# Airbeamv0_01.net
KiCad netlist of a schematic drawn in EAGLE
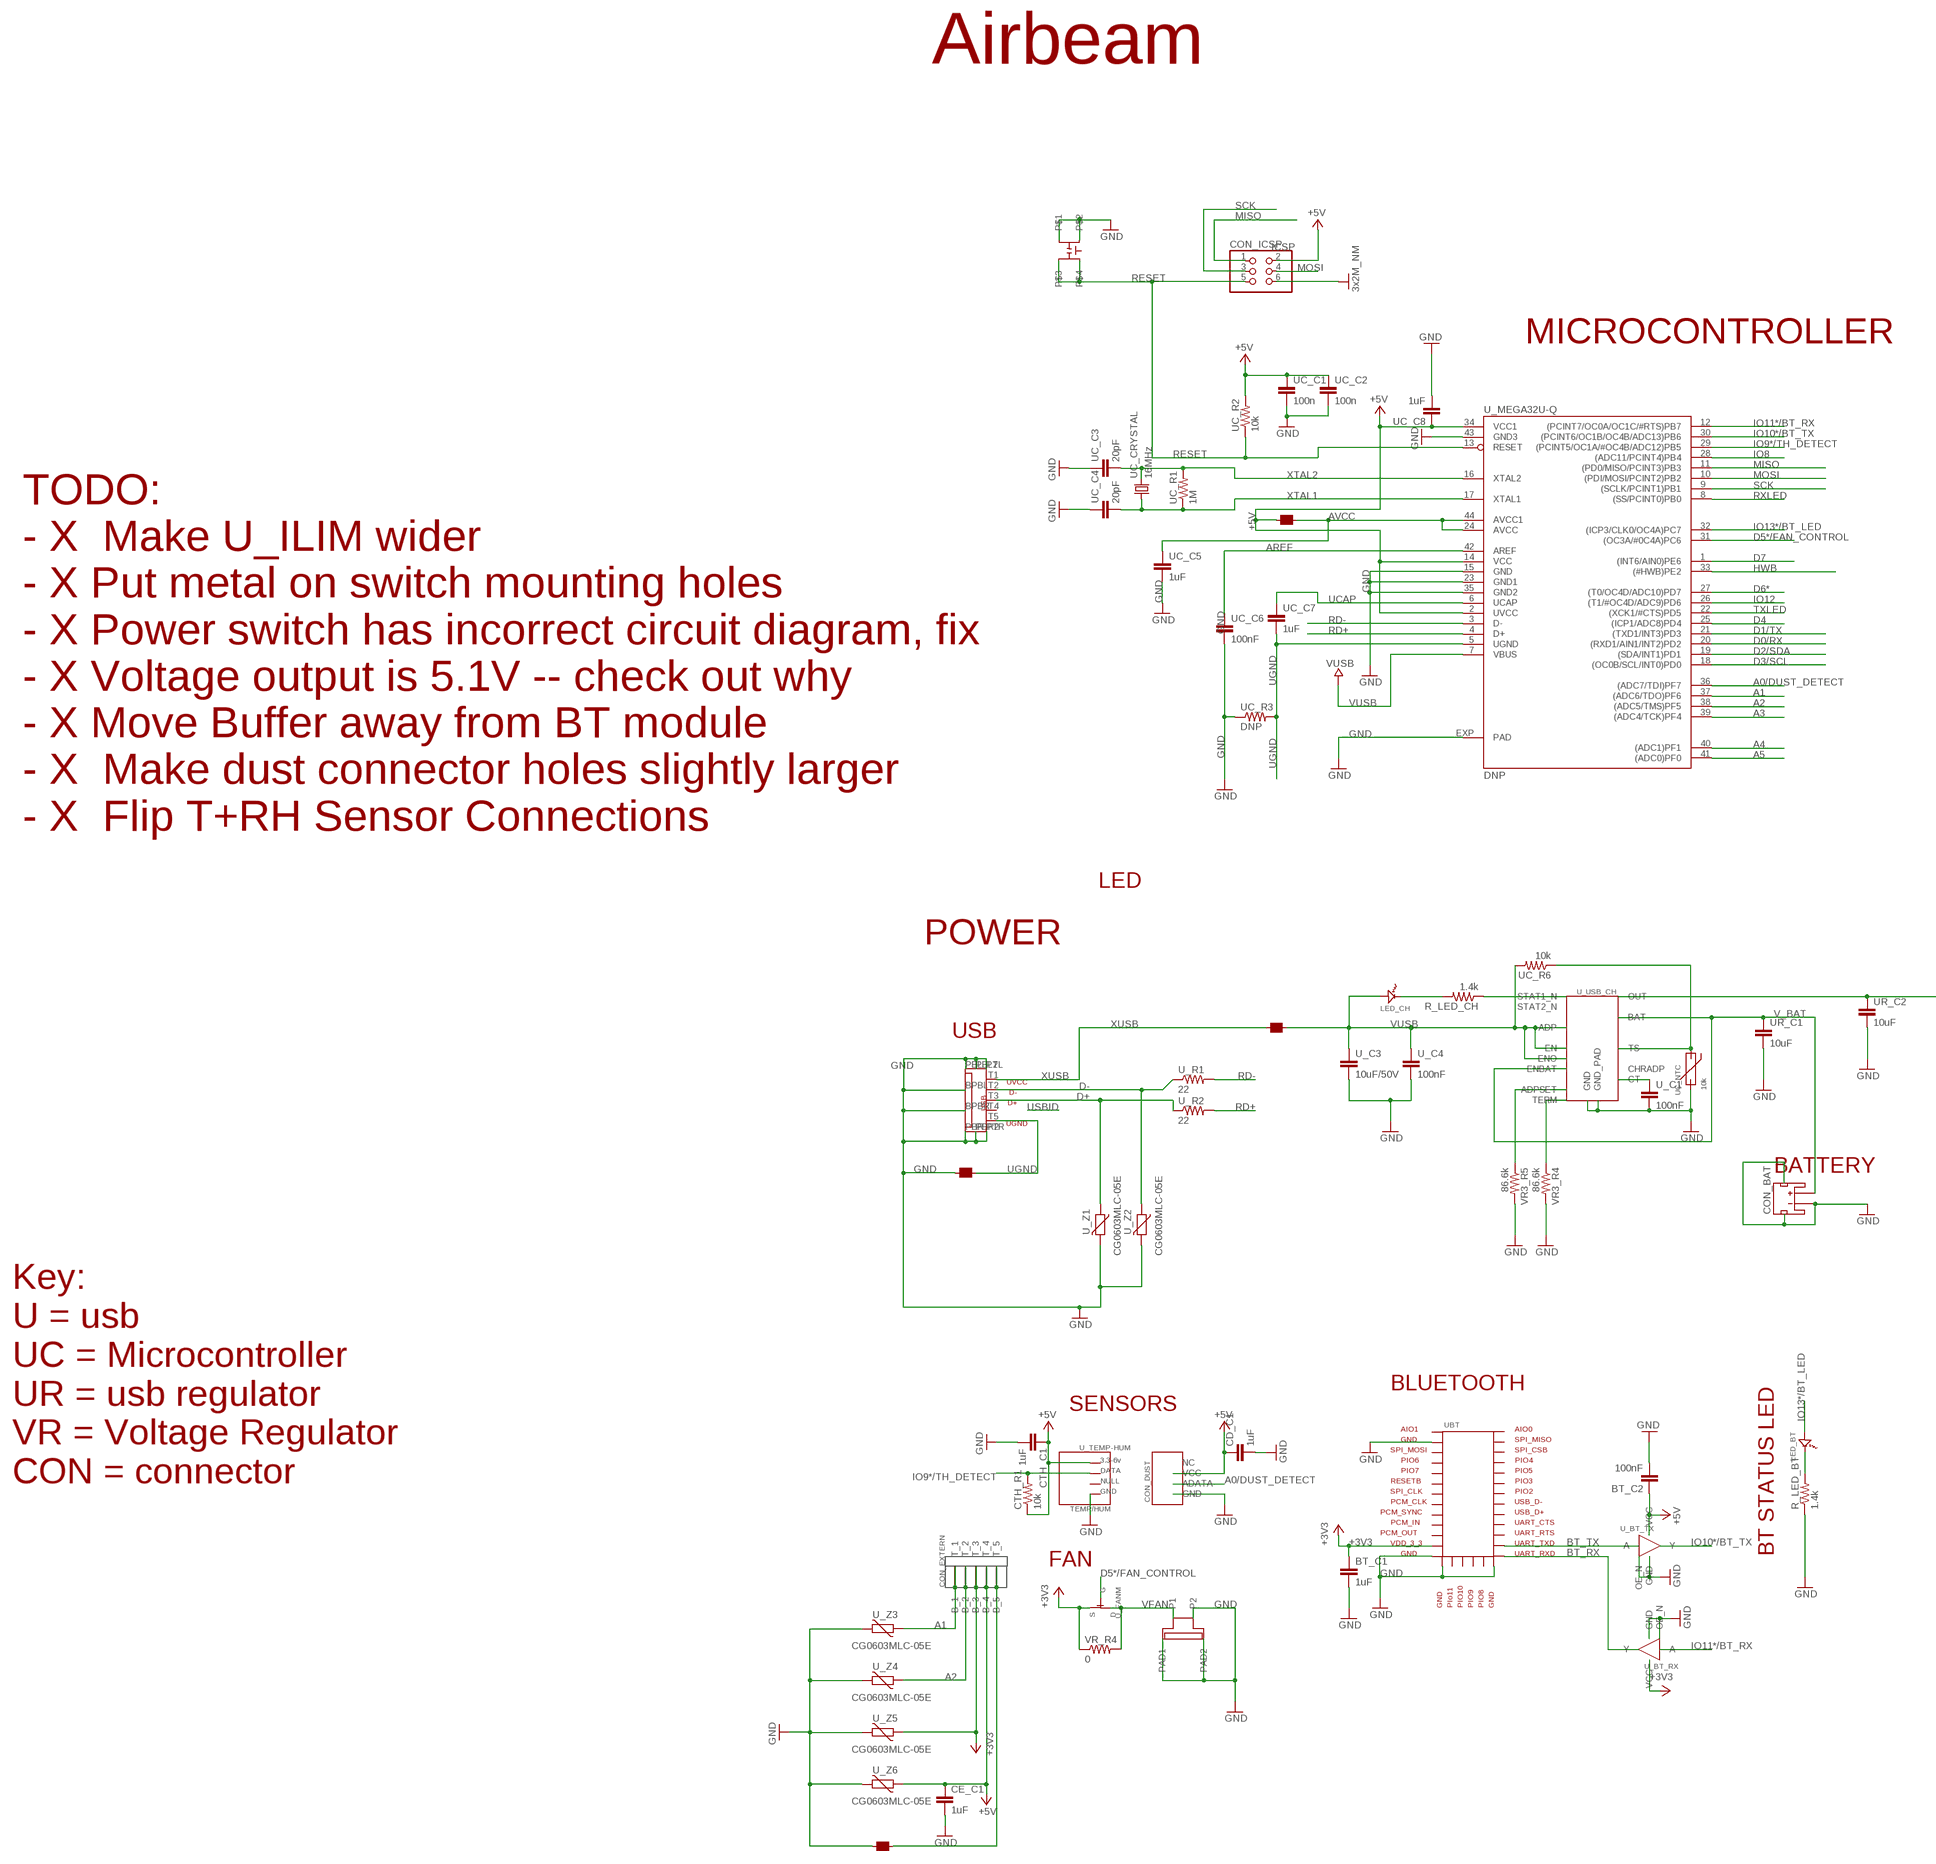
[diagram p0: schematic, sheet 1, part 1 of 2]
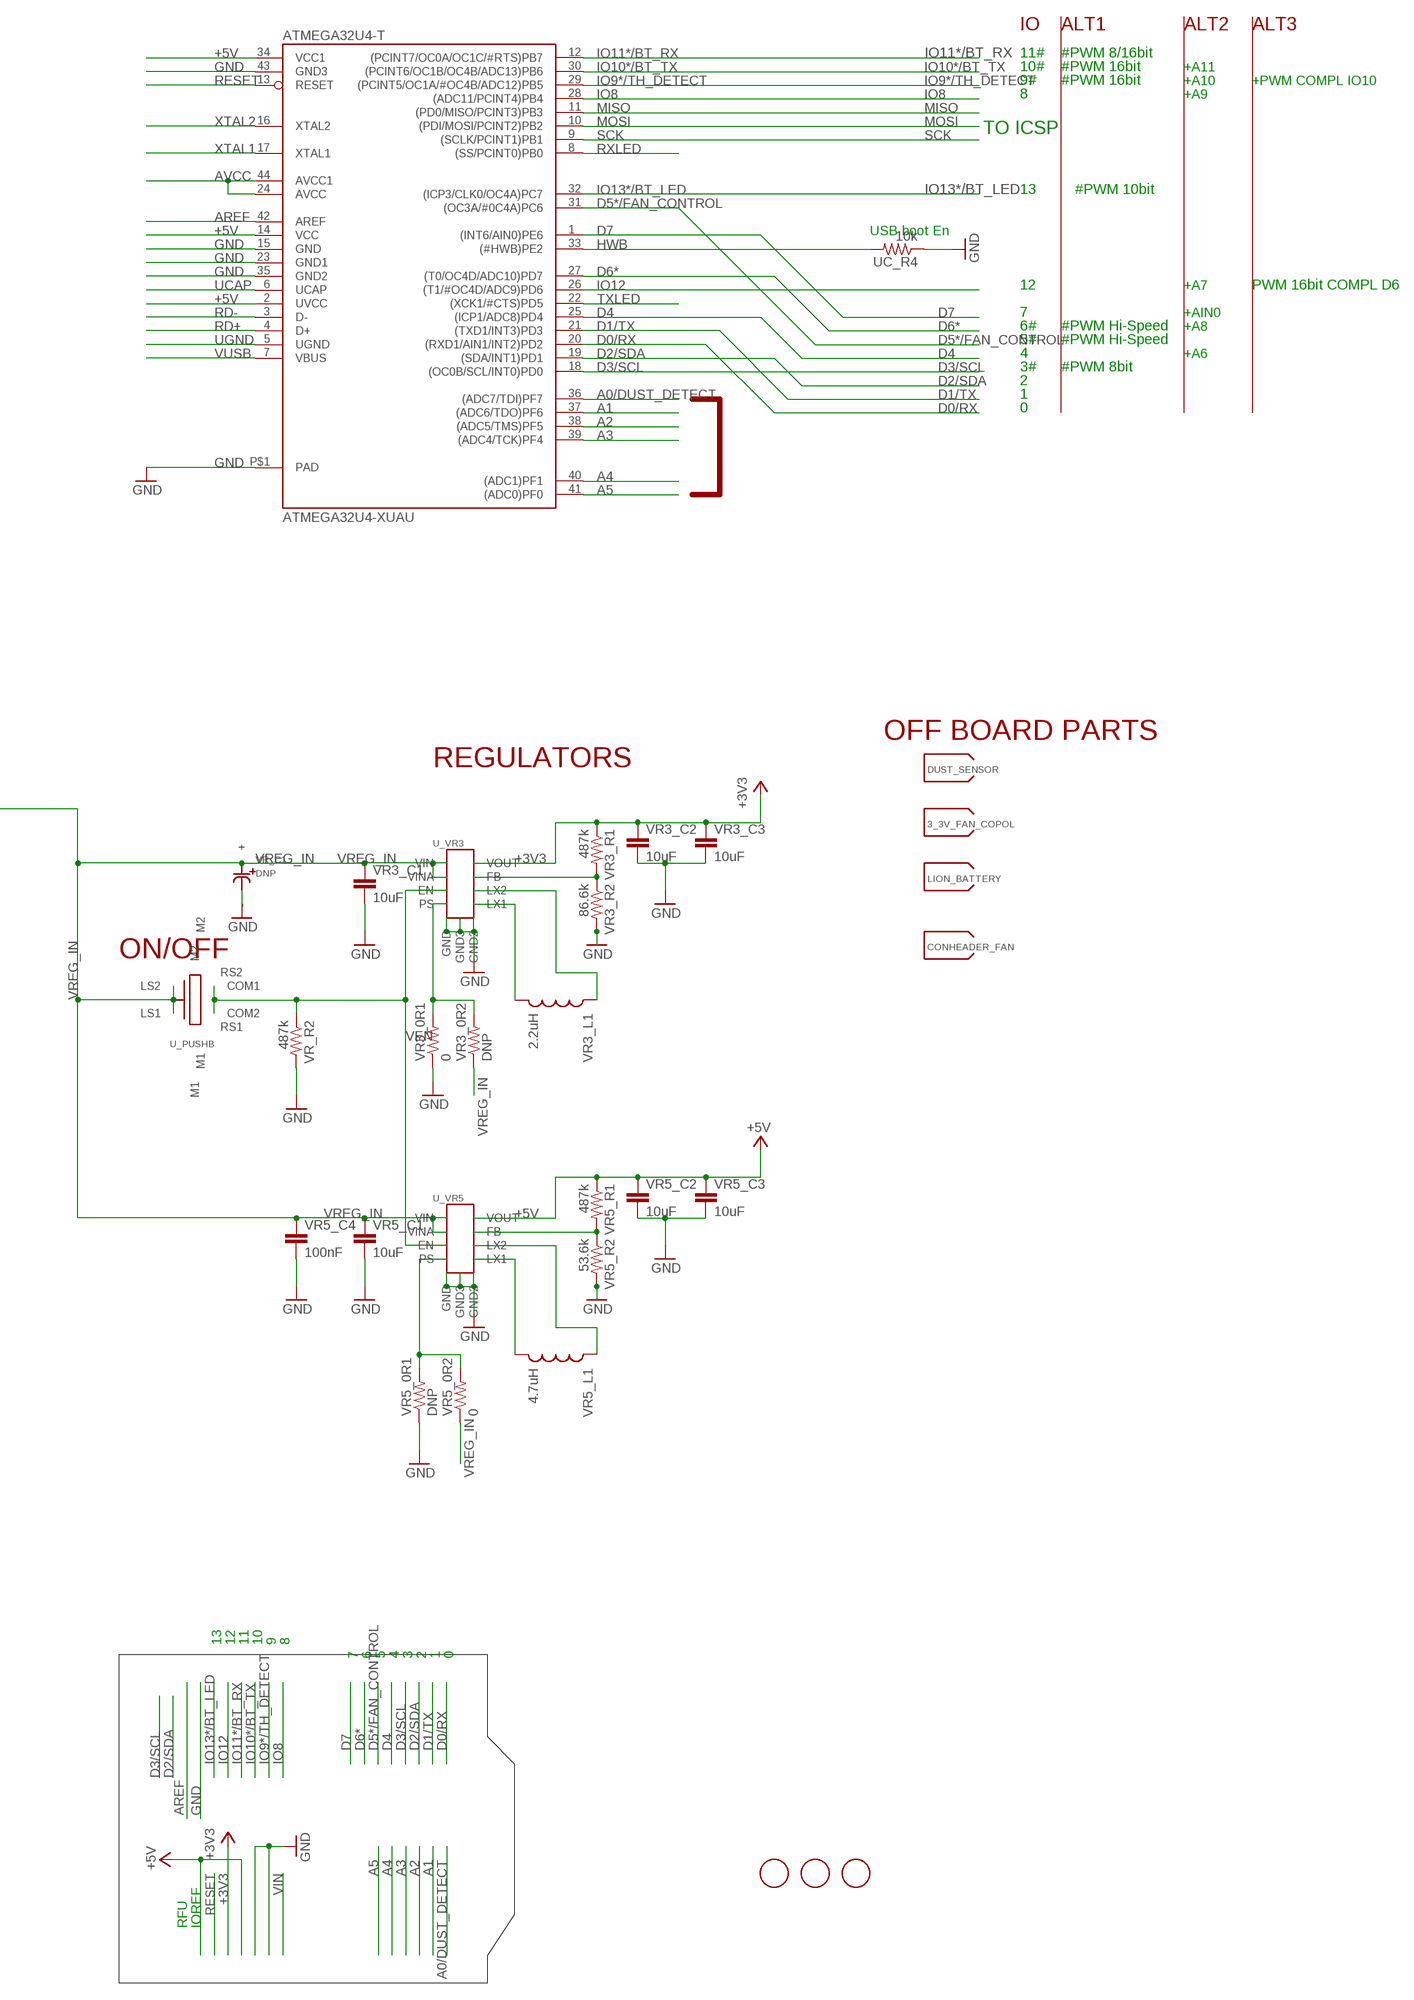
[diagram p1: schematic, sheet 1, part 2 of 2]

(export (version "E")
  (design (tool "Eeschema 10.0.6"))
  (components
    (comp (ref "3_3V_FAN_COPOL")
      (value "OFF_BOARD")
      (footprint "eagle-import:EMPTY")
      (fields (field (name "PARTNO") "F16FB-05LLC/E"))
      (libsource (lib "eagle-import") (part "PART_OFFBOARD"))
    )
    (comp (ref "ATMEGA32U4-T")
      (value "ATMEGA32U4-XUAU")
      (footprint "eagle-import:TQFP44-PAD")
      (fields (field (name "PARTNO") "ATMEGA32U4-AU"))
      (libsource (lib "eagle-import") (part "ATMEGA32U4-XUAU"))
    )
    (comp (ref "BT_C1")
      (value "1uF")
      (footprint "eagle-import:0603-CAP")
      (fields (field (name "PARTNO") "C1608X5R1C105K080AA"))
      (libsource (lib "eagle-import") (part "CAP0603-CAP"))
    )
    (comp (ref "BT_C2")
      (value "100nF")
      (footprint "eagle-import:0603-CAP")
      (fields (field (name "PARTNO") "C1608X7R1E104K080AA"))
      (libsource (lib "eagle-import") (part "CAP0603-CAP"))
    )
    (comp (ref "CA_FB1")
      (value "FERITE_BEAD")
      (footprint "eagle-import:U_FB1")
      (fields (field (name "PARTNO") "MH2029-600Y"))
      (libsource (lib "eagle-import") (part "FERITE_BEAD"))
    )
    (comp (ref "CD_C1")
      (value "1uF")
      (footprint "eagle-import:0603-CAP")
      (fields (field (name "PARTNO") "C1608X5R1C105K080AA"))
      (libsource (lib "eagle-import") (part "CAP0603-CAP"))
    )
    (comp (ref "CE_C1")
      (value "1uF")
      (footprint "eagle-import:0603-CAP")
      (fields (field (name "PARTNO") "C1608X5R1C105K080AA"))
      (libsource (lib "eagle-import") (part "CAP0603-CAP"))
    )
    (comp (ref "CONHEADER_FAN")
      (value "OFF_BOARD")
      (footprint "eagle-import:EMPTY")
      (fields (field (name "PARTNO") "02SUR-32S"))
      (libsource (lib "eagle-import") (part "PART_OFFBOARD"))
    )
    (comp (ref "CON_BAT")
      (value "CON_BAT")
      (footprint "eagle-import:JST-2-SMD")
      (fields (field (name "PARTNO") "S2B-PH-SM4-TB(LF)(SN)"))
      (libsource (lib "eagle-import") (part "JST_2MM_MALE"))
    )
    (comp (ref "CON_DUST")
      (value "CON_DUST")
      (footprint "eagle-import:S4B-EH")
      (fields (field (name "PARTNO") "S4B-EH"))
      (libsource (lib "eagle-import") (part "CON_DUST"))
    )
    (comp (ref "CON_EXTERN")
      (value "TBLOCK_5")
      (footprint "eagle-import:TBLOCK_5")
      (fields (field (name "PARTNO") "1770911"))
      (libsource (lib "eagle-import") (part "TBLOCK_5"))
    )
    (comp (ref "CON_FAN")
      (value "SUR_2PIN")
      (footprint "eagle-import:JST-0.8MM")
      (fields (field (name "PARTNO") "SM02B-SURS-TF"))
      (libsource (lib "eagle-import") (part "SUR_2PIN"))
    )
    (comp (ref "CON_ICSP")
      (value "ICSP")
      (footprint "eagle-import:2X03")
      (fields (field (name "PARTNO") "67997-206HLF "))
      (libsource (lib "eagle-import") (part "PINHD-2X3"))
    )
    (comp (ref "CON_USB")
      (value "USB-FCI")
      (footprint "eagle-import:USB-FCI")
      (fields (field (name "PARTNO") "10103594-0001LF"))
      (libsource (lib "eagle-import") (part "USB-FCI"))
    )
    (comp (ref "CTH_C1")
      (value "1uF")
      (footprint "eagle-import:0603-CAP")
      (fields (field (name "PARTNO") "C1608X5R1C105K080AA"))
      (libsource (lib "eagle-import") (part "CAP0603-CAP"))
    )
    (comp (ref "CTH_R1")
      (value "10k")
      (footprint "eagle-import:0603-RES")
      (fields (field (name "PARTNO") "RC0603JR-0710KL"))
      (libsource (lib "eagle-import") (part "RESISTOR0603-RES"))
    )
    (comp (ref "DUST_SENSOR")
      (value "OFF_BOARD")
      (footprint "eagle-import:EMPTY")
      (fields (field (name "PARTNO") "PPD60PV-T2"))
      (libsource (lib "eagle-import") (part "PART_OFFBOARD"))
    )
    (comp (ref "FID1")
      (value "FIDUCIALMOUNT")
      (footprint "eagle-import:FIDUCIA-MOUNT")
      (fields (field (name "PARTNO") "DNP"))
      (libsource (lib "eagle-import") (part "FIDUCIALMOUNT"))
    )
    (comp (ref "FID2")
      (value "FIDUCIALMOUNT")
      (footprint "eagle-import:FIDUCIA-MOUNT")
      (fields (field (name "PARTNO") "DNP"))
      (libsource (lib "eagle-import") (part "FIDUCIALMOUNT"))
    )
    (comp (ref "FID3")
      (value "FIDUCIALMOUNT")
      (footprint "eagle-import:FIDUCIA-MOUNT")
      (fields (field (name "PARTNO") "DNP"))
      (libsource (lib "eagle-import") (part "FIDUCIALMOUNT"))
    )
    (comp (ref "LED_BT")
      (value "LED")
      (footprint "eagle-import:LED_550")
      (fields (field (name "PARTNO") "550-1107F "))
      (libsource (lib "eagle-import") (part "LED"))
    )
    (comp (ref "LED_CH")
      (value "LED")
      (footprint "eagle-import:LED_550")
      (fields (field (name "PARTNO") "550-1307F"))
      (libsource (lib "eagle-import") (part "LED"))
    )
    (comp (ref "LION_BATTERY")
      (value "OFF_BOARD")
      (footprint "eagle-import:EMPTY")
      (fields (field (name "PARTNO") "585460_2000mAh"))
      (libsource (lib "eagle-import") (part "PART_OFFBOARD"))
    )
    (comp (ref "RESET_SWITCH")
      (value "DNP")
      (footprint "eagle-import:SWITCH_TACTILE")
      (fields (field (name "PARTNO") "TL3315NF250Q"))
      (libsource (lib "eagle-import") (part "SWITCH"))
    )
    (comp (ref "R_LED_BT")
      (value "1.4k")
      (footprint "eagle-import:0603-RES")
      (fields (field (name "PARTNO") "RC0603FR-071K4L"))
      (libsource (lib "eagle-import") (part "RESISTOR0603-RES"))
    )
    (comp (ref "R_LED_CH")
      (value "1.4k")
      (footprint "eagle-import:0603-RES")
      (fields (field (name "PARTNO") "RC0603FR-071K4L"))
      (libsource (lib "eagle-import") (part "RESISTOR0603-RES"))
    )
    (comp (ref "UBT")
      (value "BT-NVC-MDCS42A")
      (footprint "eagle-import:BT_NVC-MDCS42A")
      (fields (field (name "PARTNO") "NVC-MDCS42A"))
      (libsource (lib "eagle-import") (part "BT-NVC-MDCS42A"))
    )
    (comp (ref "UC_C1")
      (value "100n")
      (footprint "eagle-import:0603-CAP")
      (fields (field (name "PARTNO") "C1608X7R1E104K080AA"))
      (libsource (lib "eagle-import") (part "CAP0603-CAP"))
    )
    (comp (ref "UC_C2")
      (value "100n")
      (footprint "eagle-import:0603-CAP")
      (fields (field (name "PARTNO") "C1608X7R1E104K080AA"))
      (libsource (lib "eagle-import") (part "CAP0603-CAP"))
    )
    (comp (ref "UC_C3")
      (value "20pF")
      (footprint "eagle-import:0603-CAP")
      (fields (field (name "PARTNO") "CL10C200JB8NNNC"))
      (libsource (lib "eagle-import") (part "CAP0603-CAP"))
    )
    (comp (ref "UC_C4")
      (value "20pF")
      (footprint "eagle-import:0603-CAP")
      (fields (field (name "PARTNO") "CL10C200JB8NNNC"))
      (libsource (lib "eagle-import") (part "CAP0603-CAP"))
    )
    (comp (ref "UC_C5")
      (value "1uF")
      (footprint "eagle-import:0603-CAP")
      (fields (field (name "PARTNO") "C1608X5R1C105K080AA"))
      (libsource (lib "eagle-import") (part "CAP0603-CAP"))
    )
    (comp (ref "UC_C6")
      (value "100nF")
      (footprint "eagle-import:0603-CAP")
      (fields (field (name "PARTNO") "C1608X7R1E104K080AA"))
      (libsource (lib "eagle-import") (part "CAP0603-CAP"))
    )
    (comp (ref "UC_C7")
      (value "1uF")
      (footprint "eagle-import:0603-CAP")
      (fields (field (name "PARTNO") "C1608X5R1C105K080AA"))
      (libsource (lib "eagle-import") (part "CAP0603-CAP"))
    )
    (comp (ref "UC_C8")
      (value "1uF")
      (footprint "eagle-import:0603-CAP")
      (fields (field (name "PARTNO") "C1608X5R1C105K080AA"))
      (libsource (lib "eagle-import") (part "CAP0603-CAP"))
    )
    (comp (ref "UC_CRYSTAL")
      (value "16MHz")
      (footprint "eagle-import:HC49UP")
      (fields (field (name "PARTNO") "ECS-160-20-3X-TR "))
      (libsource (lib "eagle-import") (part "CRYSTALSMD"))
    )
    (comp (ref "UC_NTC")
      (value "10k")
      (footprint "eagle-import:0402")
      (fields (field (name "PARTNO") "ERT-J0EM103J ") (field (name "PARTNO_1") "ERT-J0EM103J"))
      (libsource (lib "eagle-import") (part "THERMISTOR0402"))
    )
    (comp (ref "UC_R1")
      (value "1M")
      (footprint "eagle-import:0603-RES")
      (fields (field (name "PARTNO") "RC0603FR-071ML"))
      (libsource (lib "eagle-import") (part "RESISTOR0603-RES"))
    )
    (comp (ref "UC_R2")
      (value "10k")
      (footprint "eagle-import:0603-RES")
      (fields (field (name "PARTNO") "RC0603JR-0710KL"))
      (libsource (lib "eagle-import") (part "RESISTOR0603-RES"))
    )
    (comp (ref "UC_R3")
      (value "DNP")
      (footprint "eagle-import:0603-RES")
      (fields (field (name "PARTNO") "RC0603JR-070RL"))
      (libsource (lib "eagle-import") (part "RESISTOR0603-RES"))
    )
    (comp (ref "UC_R4")
      (value "10k")
      (footprint "eagle-import:0603-RES")
      (fields (field (name "PARTNO") "RC0603JR-0710KL"))
      (libsource (lib "eagle-import") (part "RESISTOR0603-RES"))
    )
    (comp (ref "UC_R6")
      (value "10k")
      (footprint "eagle-import:0603-RES")
      (fields (field (name "PARTNO") "RC0603JR-0710KL"))
      (libsource (lib "eagle-import") (part "RESISTOR0603-RES"))
    )
    (comp (ref "UR_C1")
      (value "10uF")
      (footprint "eagle-import:0805")
      (fields (field (name "PARTNO") "C2012X5R1C106K085AC"))
      (libsource (lib "eagle-import") (part "CAP0805"))
    )
    (comp (ref "UR_C2")
      (value "10uF")
      (footprint "eagle-import:0805")
      (fields (field (name "PARTNO") "C2012X5R1C106K085AC"))
      (libsource (lib "eagle-import") (part "CAP0805"))
    )
    (comp (ref "U_BT_RX")
      (value "V_BUFFER")
      (footprint "eagle-import:SOT23-5")
      (fields (field (name "PARTNO") "SN74LVC1G125DBVR"))
      (libsource (lib "eagle-import") (part "V_BUFFER"))
    )
    (comp (ref "U_BT_TX")
      (value "V_BUFFER")
      (footprint "eagle-import:SOT23-5")
      (fields (field (name "PARTNO") "SN74LVC1G125DBVR"))
      (libsource (lib "eagle-import") (part "V_BUFFER"))
    )
    (comp (ref "U_C1")
      (value "100nF")
      (footprint "eagle-import:0603-CAP")
      (fields (field (name "PARTNO") "C1608X7R1E104K080AA"))
      (libsource (lib "eagle-import") (part "CAP0603-CAP"))
    )
    (comp (ref "U_C3")
      (value "10uF/50V")
      (footprint "eagle-import:1206")
      (fields (field (name "PARTNO") "CL31A106KBHNNNE "))
      (libsource (lib "eagle-import") (part "CAP1206"))
    )
    (comp (ref "U_C4")
      (value "100nF")
      (footprint "eagle-import:0603-CAP")
      (fields (field (name "PARTNO") "CC0603ZRY5V9BB104"))
      (libsource (lib "eagle-import") (part "CAP0603-CAP"))
    )
    (comp (ref "U_FANM")
      (value "DNP")
      (footprint "eagle-import:SOT23")
      (fields (field (name "PARTNO") "NDS331N"))
      (libsource (lib "eagle-import") (part "MOSFET-N"))
    )
    (comp (ref "U_FB1")
      (value "FERITE_BEAD")
      (footprint "eagle-import:U_FB1")
      (fields (field (name "PARTNO") "MH2029-600Y"))
      (libsource (lib "eagle-import") (part "FERITE_BEAD"))
    )
    (comp (ref "U_FB2")
      (value "FERITE_BEAD")
      (footprint "eagle-import:U_FB1")
      (fields (field (name "PARTNO") "MH2029-600Y"))
      (libsource (lib "eagle-import") (part "FERITE_BEAD"))
    )
    (comp (ref "U_FB3")
      (value "FERITE_BEAD")
      (footprint "eagle-import:U_FB1")
      (fields (field (name "PARTNO") "MH2029-600Y"))
      (libsource (lib "eagle-import") (part "FERITE_BEAD"))
    )
    (comp (ref "U_MEGA32U-Q")
      (value "DNP")
      (footprint "eagle-import:QFN44ML7X7")
      (fields (field (name "PARTNO") "ATMEGA32U4-MU "))
      (libsource (lib "eagle-import") (part "ATMEGA32U4-XUMU"))
    )
    (comp (ref "U_PUSHB")
      (value "PUSHBUTTON")
      (footprint "eagle-import:PUSHBUTTON")
      (fields (field (name "PARTNO") "LC2259EENP"))
      (libsource (lib "eagle-import") (part "PUSHBUTTON"))
    )
    (comp (ref "U_R1")
      (value "22")
      (footprint "eagle-import:0603-RES")
      (fields (field (name "PARTNO") "RC0603JR-0722RL"))
      (libsource (lib "eagle-import") (part "RESISTOR0603-RES"))
    )
    (comp (ref "U_R2")
      (value "22")
      (footprint "eagle-import:0603-RES")
      (fields (field (name "PARTNO") "RC0603JR-0722RL"))
      (libsource (lib "eagle-import") (part "RESISTOR0603-RES"))
    )
    (comp (ref "U_TEMP-HUM")
      (value "RHT03")
      (footprint "eagle-import:RHT03")
      (fields (field (name "PARTNO") "RHT03 "))
      (libsource (lib "eagle-import") (part "RHT03"))
    )
    (comp (ref "U_USB_CH")
      (value "USB-BATTERY_LOAD")
      (footprint "eagle-import:TDFN33-14")
      (fields (field (name "PARTNO") "AAT3672IWO-4.2-1-T1") (field (name "PARTNO_1") "AAT3672IWO-4.2-1-T1"))
      (libsource (lib "eagle-import") (part "USB-BATTERY_LOAD"))
    )
    (comp (ref "U_VR3")
      (value "VREG-RTEC6150")
      (footprint "eagle-import:WFDFN-10")
      (fields (field (name "PARTNO") "RT6150BGQW"))
      (libsource (lib "eagle-import") (part "VREG-RTEC6150"))
    )
    (comp (ref "U_VR5")
      (value "VREG-RTEC6150")
      (footprint "eagle-import:WFDFN-10")
      (fields (field (name "PARTNO") "RT6150BGQW"))
      (libsource (lib "eagle-import") (part "VREG-RTEC6150"))
    )
    (comp (ref "U_Z1")
      (value "CG0603MLC-05E")
      (footprint "eagle-import:CT_CN0603")
      (libsource (lib "eagle-import") (part "VARISTORCN0603"))
    )
    (comp (ref "U_Z2")
      (value "CG0603MLC-05E")
      (footprint "eagle-import:CT_CN0603")
      (libsource (lib "eagle-import") (part "VARISTORCN0603"))
    )
    (comp (ref "U_Z3")
      (value "CG0603MLC-05E")
      (footprint "eagle-import:CT_CN0603")
      (libsource (lib "eagle-import") (part "VARISTORCN0603"))
    )
    (comp (ref "U_Z4")
      (value "CG0603MLC-05E")
      (footprint "eagle-import:CT_CN0603")
      (libsource (lib "eagle-import") (part "VARISTORCN0603"))
    )
    (comp (ref "U_Z5")
      (value "CG0603MLC-05E")
      (footprint "eagle-import:CT_CN0603")
      (libsource (lib "eagle-import") (part "VARISTORCN0603"))
    )
    (comp (ref "U_Z6")
      (value "CG0603MLC-05E")
      (footprint "eagle-import:CT_CN0603")
      (libsource (lib "eagle-import") (part "VARISTORCN0603"))
    )
    (comp (ref "VR3_0R1")
      (value "0")
      (footprint "eagle-import:0603-RES")
      (fields (field (name "PARTNO") "RC0603JR-070RL"))
      (libsource (lib "eagle-import") (part "RESISTOR0603-RES"))
    )
    (comp (ref "VR3_0R2")
      (value "DNP")
      (footprint "eagle-import:0603-RES")
      (fields (field (name "PARTNO") "RC0603JR-070RL"))
      (libsource (lib "eagle-import") (part "RESISTOR0603-RES"))
    )
    (comp (ref "VR3_C1")
      (value "10uF")
      (footprint "eagle-import:0805")
      (fields (field (name "PARTNO") "C2012X5R1C106K085AC"))
      (libsource (lib "eagle-import") (part "CAP0805"))
    )
    (comp (ref "VR3_C2")
      (value "10uF")
      (footprint "eagle-import:0805")
      (fields (field (name "PARTNO") "C2012X5R1C106K085AC"))
      (libsource (lib "eagle-import") (part "CAP0805"))
    )
    (comp (ref "VR3_C3")
      (value "10uF")
      (footprint "eagle-import:0805")
      (fields (field (name "PARTNO") "C2012X5R1C106K085AC"))
      (libsource (lib "eagle-import") (part "CAP0805"))
    )
    (comp (ref "VR3_L1")
      (value "2.2uH")
      (footprint "eagle-import:1210")
      (fields (field (name "PARTNO") "BRL3225T2R2M"))
      (libsource (lib "eagle-import") (part "INDUCTOR1210"))
    )
    (comp (ref "VR3_R1")
      (value "487k")
      (footprint "eagle-import:0603-RES")
      (fields (field (name "PARTNO") "ERJ-3EKF4873V"))
      (libsource (lib "eagle-import") (part "RESISTOR0603"))
    )
    (comp (ref "VR3_R2")
      (value "86.6k")
      (footprint "eagle-import:0603-RES")
      (fields (field (name "PARTNO") "ERJ-3EKF8662V"))
      (libsource (lib "eagle-import") (part "RESISTOR0603"))
    )
    (comp (ref "VR3_R4")
      (value "86.6k")
      (footprint "eagle-import:0603-RES")
      (fields (field (name "PARTNO") "ERJ-3EKF8662V"))
      (libsource (lib "eagle-import") (part "RESISTOR0603"))
    )
    (comp (ref "VR3_R5")
      (value "86.6k")
      (footprint "eagle-import:0603-RES")
      (fields (field (name "PARTNO") "ERJ-3EKF8662V"))
      (libsource (lib "eagle-import") (part "RESISTOR0603"))
    )
    (comp (ref "VR5_0R1")
      (value "DNP")
      (footprint "eagle-import:0603-RES")
      (fields (field (name "PARTNO") "RC0603JR-070RL"))
      (libsource (lib "eagle-import") (part "RESISTOR0603-RES"))
    )
    (comp (ref "VR5_0R2")
      (value "0")
      (footprint "eagle-import:0603-RES")
      (fields (field (name "PARTNO") "RC0603JR-070RL"))
      (libsource (lib "eagle-import") (part "RESISTOR0603-RES"))
    )
    (comp (ref "VR5_C1")
      (value "10uF")
      (footprint "eagle-import:0805")
      (fields (field (name "PARTNO") "C2012X5R1C106K085AC"))
      (libsource (lib "eagle-import") (part "CAP0805"))
    )
    (comp (ref "VR5_C2")
      (value "10uF")
      (footprint "eagle-import:0805")
      (fields (field (name "PARTNO") "C2012X5R1C106K085AC"))
      (libsource (lib "eagle-import") (part "CAP0805"))
    )
    (comp (ref "VR5_C3")
      (value "10uF")
      (footprint "eagle-import:0805")
      (fields (field (name "PARTNO") "C2012X5R1C106K085AC"))
      (libsource (lib "eagle-import") (part "CAP0805"))
    )
    (comp (ref "VR5_C4")
      (value "100nF")
      (footprint "eagle-import:0603-CAP")
      (fields (field (name "PARTNO") "C1608X7R1E104K080AA"))
      (libsource (lib "eagle-import") (part "CAP0603-CAP"))
    )
    (comp (ref "VR5_L1")
      (value "4.7uH")
      (footprint "eagle-import:1210")
      (fields (field (name "PARTNO") "CBC3225T4R7MR"))
      (libsource (lib "eagle-import") (part "INDUCTOR1210"))
    )
    (comp (ref "VR5_R1")
      (value "487k")
      (footprint "eagle-import:0603-RES")
      (fields (field (name "PARTNO") "ERJ-3EKF4873V"))
      (libsource (lib "eagle-import") (part "RESISTOR0603"))
    )
    (comp (ref "VR5_R2")
      (value "53.6k")
      (footprint "eagle-import:0603-RES")
      (fields (field (name "PARTNO") "RC0805FR-0753K6L"))
      (libsource (lib "eagle-import") (part "RESISTOR0603"))
    )
    (comp (ref "VR_C1")
      (value "DNP")
      (footprint "eagle-import:2917_CAP")
      (fields (field (name "PARTNO") "T491D107K010AT "))
      (libsource (lib "eagle-import") (part "CAP_POL120UF"))
    )
    (comp (ref "VR_R2")
      (value "487k")
      (footprint "eagle-import:0603-RES")
      (fields (field (name "PARTNO") "ERJ-3EKF4873V"))
      (libsource (lib "eagle-import") (part "RESISTOR0603"))
    )
    (comp (ref "VR_R4")
      (value "0")
      (footprint "eagle-import:0603-RES")
      (fields (field (name "PARTNO") "RC0603JR-070RL"))
      (libsource (lib "eagle-import") (part "RESISTOR0603"))
    )
  )
  (nets
    (net (code "1") (name "+3V3") (class "Default")
      (node (ref "BT_C1") (pin "1") (pinfunction "1_1") (pintype "passive"))
      (node (ref "CON_EXTERN") (pin "B_3") (pinfunction "B_3_B_3") (pintype "bidirectional"))
      (node (ref "CON_EXTERN") (pin "T_3") (pinfunction "T_3_T_3") (pintype "bidirectional"))
      (node (ref "UBT") (pin "P$12") (pinfunction "P$12_P$12") (pintype "bidirectional"))
      (node (ref "U_BT_RX") (pin "5") (pinfunction "VCC_5") (pintype "bidirectional"))
      (node (ref "U_FANM") (pin "2") (pinfunction "P$2_2") (pintype "bidirectional"))
      (node (ref "U_VR3") (pin "P$1") (pinfunction "VOUT_P$1") (pintype "bidirectional"))
      (node (ref "U_Z5") (pin "1") (pinfunction "1_1") (pintype "passive"))
      (node (ref "VR3_C2") (pin "1") (pinfunction "1_1") (pintype "passive"))
      (node (ref "VR3_C3") (pin "1") (pinfunction "1_1") (pintype "passive"))
      (node (ref "VR3_R1") (pin "1") (pinfunction "1_1") (pintype "passive"))
      (node (ref "VR_R4") (pin "1") (pinfunction "1_1") (pintype "passive"))
    )
    (net (code "2") (name "+5V") (class "Default")
      (node (ref "ATMEGA32U4-T") (pin "14") (pinfunction "VCC_14") (pintype "power_in"))
      (node (ref "ATMEGA32U4-T") (pin "2") (pinfunction "UVCC_2") (pintype "power_in"))
      (node (ref "ATMEGA32U4-T") (pin "34") (pinfunction "VCC1_34") (pintype "power_in"))
      (node (ref "BT_C2") (pin "1") (pinfunction "1_1") (pintype "passive"))
      (node (ref "CD_C1") (pin "1") (pinfunction "1_1") (pintype "passive"))
      (node (ref "CE_C1") (pin "1") (pinfunction "1_1") (pintype "passive"))
      (node (ref "CON_DUST") (pin "P$3") (pinfunction "VCC_P$3") (pintype "bidirectional"))
      (node (ref "CON_EXTERN") (pin "B_4") (pinfunction "B_4_B_4") (pintype "bidirectional"))
      (node (ref "CON_EXTERN") (pin "T_4") (pinfunction "T_4_T_4") (pintype "bidirectional"))
      (node (ref "CON_ICSP") (pin "2") (pinfunction "2_2") (pintype "passive"))
      (node (ref "CTH_C1") (pin "1") (pinfunction "1_1") (pintype "passive"))
      (node (ref "CTH_R1") (pin "1") (pinfunction "1_1") (pintype "passive"))
      (node (ref "UC_C1") (pin "1") (pinfunction "1_1") (pintype "passive"))
      (node (ref "UC_C2") (pin "1") (pinfunction "1_1") (pintype "passive"))
      (node (ref "UC_C8") (pin "1") (pinfunction "1_1") (pintype "passive"))
      (node (ref "UC_R2") (pin "2") (pinfunction "2_2") (pintype "passive"))
      (node (ref "U_BT_TX") (pin "5") (pinfunction "VCC_5") (pintype "bidirectional"))
      (node (ref "U_FB2") (pin "P$1") (pinfunction "P$1_P$1") (pintype "passive"))
      (node (ref "U_MEGA32U-Q") (pin "14") (pinfunction "VCC_14") (pintype "power_in"))
      (node (ref "U_MEGA32U-Q") (pin "2") (pinfunction "UVCC_2") (pintype "power_in"))
      (node (ref "U_MEGA32U-Q") (pin "34") (pinfunction "VCC1_34") (pintype "power_in"))
      (node (ref "U_TEMP-HUM") (pin "P$1") (pinfunction "P$1_P$1") (pintype "bidirectional"))
      (node (ref "U_VR5") (pin "P$1") (pinfunction "VOUT_P$1") (pintype "bidirectional"))
      (node (ref "U_Z6") (pin "1") (pinfunction "1_1") (pintype "passive"))
      (node (ref "VR5_C2") (pin "1") (pinfunction "1_1") (pintype "passive"))
      (node (ref "VR5_C3") (pin "1") (pinfunction "1_1") (pintype "passive"))
      (node (ref "VR5_R1") (pin "1") (pinfunction "1_1") (pintype "passive"))
    )
    (net (code "3") (name "/A0{slash}DUST_DETECT") (class "Default")
      (node (ref "ATMEGA32U4-T") (pin "36") (pinfunction "(ADC7/TDI)PF7_36") (pintype "bidirectional"))
      (node (ref "CON_DUST") (pin "P$2") (pinfunction "ADATA_P$2") (pintype "bidirectional"))
      (node (ref "U_MEGA32U-Q") (pin "36") (pinfunction "(ADC7/TDI)PF7_36") (pintype "bidirectional"))
    )
    (net (code "4") (name "/A1") (class "Default")
      (node (ref "ATMEGA32U4-T") (pin "37") (pinfunction "(ADC6/TDO)PF6_37") (pintype "bidirectional"))
      (node (ref "CON_EXTERN") (pin "B_1") (pinfunction "B_1_B_1") (pintype "bidirectional"))
      (node (ref "CON_EXTERN") (pin "T_1") (pinfunction "T_1_T_1") (pintype "bidirectional"))
      (node (ref "U_MEGA32U-Q") (pin "37") (pinfunction "(ADC6/TDO)PF6_37") (pintype "bidirectional"))
      (node (ref "U_Z3") (pin "1") (pinfunction "1_1") (pintype "passive"))
    )
    (net (code "5") (name "/A2") (class "Default")
      (node (ref "ATMEGA32U4-T") (pin "38") (pinfunction "(ADC5/TMS)PF5_38") (pintype "bidirectional"))
      (node (ref "CON_EXTERN") (pin "B_2") (pinfunction "B_2_B_2") (pintype "bidirectional"))
      (node (ref "CON_EXTERN") (pin "T_2") (pinfunction "T_2_T_2") (pintype "bidirectional"))
      (node (ref "U_MEGA32U-Q") (pin "38") (pinfunction "(ADC5/TMS)PF5_38") (pintype "bidirectional"))
      (node (ref "U_Z4") (pin "1") (pinfunction "1_1") (pintype "passive"))
    )
    (net (code "6") (name "/A3") (class "Default")
      (node (ref "ATMEGA32U4-T") (pin "39") (pinfunction "(ADC4/TCK)PF4_39") (pintype "bidirectional"))
      (node (ref "U_MEGA32U-Q") (pin "39") (pinfunction "(ADC4/TCK)PF4_39") (pintype "bidirectional"))
    )
    (net (code "7") (name "/A4") (class "Default")
      (node (ref "ATMEGA32U4-T") (pin "40") (pinfunction "(ADC1)PF1_40") (pintype "bidirectional"))
      (node (ref "U_MEGA32U-Q") (pin "40") (pinfunction "(ADC1)PF1_40") (pintype "bidirectional"))
    )
    (net (code "8") (name "/A5") (class "Default")
      (node (ref "ATMEGA32U4-T") (pin "41") (pinfunction "(ADC0)PF0_41") (pintype "bidirectional"))
      (node (ref "U_MEGA32U-Q") (pin "41") (pinfunction "(ADC0)PF0_41") (pintype "bidirectional"))
    )
    (net (code "9") (name "/AREF") (class "Default")
      (node (ref "ATMEGA32U4-T") (pin "42") (pinfunction "AREF_42") (pintype "power_in"))
      (node (ref "UC_C6") (pin "1") (pinfunction "1_1") (pintype "passive"))
      (node (ref "U_MEGA32U-Q") (pin "42") (pinfunction "AREF_42") (pintype "power_in"))
    )
    (net (code "10") (name "/AVCC") (class "Default")
      (node (ref "ATMEGA32U4-T") (pin "24") (pinfunction "AVCC_24") (pintype "power_in"))
      (node (ref "ATMEGA32U4-T") (pin "44") (pinfunction "AVCC1_44") (pintype "power_in"))
      (node (ref "UC_C5") (pin "1") (pinfunction "1_1") (pintype "passive"))
      (node (ref "U_FB2") (pin "P$2") (pinfunction "P$2_P$2") (pintype "passive"))
      (node (ref "U_MEGA32U-Q") (pin "24") (pinfunction "AVCC_24") (pintype "power_in"))
      (node (ref "U_MEGA32U-Q") (pin "44") (pinfunction "AVCC1_44") (pintype "power_in"))
    )
    (net (code "11") (name "/BT_RX") (class "Default")
      (node (ref "UBT") (pin "P$20") (pinfunction "P$20_P$20") (pintype "bidirectional"))
      (node (ref "U_BT_RX") (pin "4") (pinfunction "Y_4") (pintype "bidirectional"))
    )
    (net (code "12") (name "/BT_TX") (class "Default")
      (node (ref "UBT") (pin "P$21") (pinfunction "P$21_P$21") (pintype "bidirectional"))
      (node (ref "U_BT_TX") (pin "2") (pinfunction "A_2") (pintype "bidirectional"))
    )
    (net (code "13") (name "/D+") (class "Default")
      (node (ref "CON_USB") (pin "T3") (pinfunction "T3_T3") (pintype "bidirectional"))
      (node (ref "U_R2") (pin "1") (pinfunction "1_1") (pintype "passive"))
      (node (ref "U_Z1") (pin "1") (pinfunction "1_1") (pintype "passive"))
    )
    (net (code "14") (name "/D-") (class "Default")
      (node (ref "CON_USB") (pin "T2") (pinfunction "T2_T2") (pintype "bidirectional"))
      (node (ref "U_R1") (pin "1") (pinfunction "1_1") (pintype "passive"))
      (node (ref "U_Z2") (pin "1") (pinfunction "1_1") (pintype "passive"))
    )
    (net (code "15") (name "/D0{slash}RX") (class "Default")
      (node (ref "ATMEGA32U4-T") (pin "20") (pinfunction "(RXD1/AIN1/INT2)PD2_20") (pintype "bidirectional"))
      (node (ref "U_MEGA32U-Q") (pin "20") (pinfunction "(RXD1/AIN1/INT2)PD2_20") (pintype "bidirectional"))
    )
    (net (code "16") (name "/D1{slash}TX") (class "Default")
      (node (ref "ATMEGA32U4-T") (pin "21") (pinfunction "(TXD1/INT3)PD3_21") (pintype "bidirectional"))
      (node (ref "U_MEGA32U-Q") (pin "21") (pinfunction "(TXD1/INT3)PD3_21") (pintype "bidirectional"))
    )
    (net (code "17") (name "/D2{slash}SDA") (class "Default")
      (node (ref "ATMEGA32U4-T") (pin "19") (pinfunction "(SDA/INT1)PD1_19") (pintype "bidirectional"))
      (node (ref "U_MEGA32U-Q") (pin "19") (pinfunction "(SDA/INT1)PD1_19") (pintype "bidirectional"))
    )
    (net (code "18") (name "/D3{slash}SCL") (class "Default")
      (node (ref "ATMEGA32U4-T") (pin "18") (pinfunction "(OC0B/SCL/INT0)PD0_18") (pintype "bidirectional"))
      (node (ref "U_MEGA32U-Q") (pin "18") (pinfunction "(OC0B/SCL/INT0)PD0_18") (pintype "bidirectional"))
    )
    (net (code "19") (name "/D4") (class "Default")
      (node (ref "ATMEGA32U4-T") (pin "25") (pinfunction "(ICP1/ADC8)PD4_25") (pintype "bidirectional"))
      (node (ref "U_MEGA32U-Q") (pin "25") (pinfunction "(ICP1/ADC8)PD4_25") (pintype "bidirectional"))
    )
    (net (code "20") (name "/D5*{slash}FAN_CONTROL") (class "Default")
      (node (ref "ATMEGA32U4-T") (pin "31") (pinfunction "(OC3A/#0C4A)PC6_31") (pintype "bidirectional"))
      (node (ref "U_FANM") (pin "1") (pinfunction "P$1_1") (pintype "bidirectional"))
      (node (ref "U_MEGA32U-Q") (pin "31") (pinfunction "(OC3A/#0C4A)PC6_31") (pintype "bidirectional"))
    )
    (net (code "21") (name "/D6*") (class "Default")
      (node (ref "ATMEGA32U4-T") (pin "27") (pinfunction "(T0/OC4D/ADC10)PD7_27") (pintype "bidirectional"))
      (node (ref "U_MEGA32U-Q") (pin "27") (pinfunction "(T0/OC4D/ADC10)PD7_27") (pintype "bidirectional"))
    )
    (net (code "22") (name "/D7") (class "Default")
      (node (ref "ATMEGA32U4-T") (pin "1") (pinfunction "(INT6/AIN0)PE6_1") (pintype "bidirectional"))
      (node (ref "U_MEGA32U-Q") (pin "1") (pinfunction "(INT6/AIN0)PE6_1") (pintype "bidirectional"))
    )
    (net (code "23") (name "/HWB") (class "Default")
      (node (ref "ATMEGA32U4-T") (pin "33") (pinfunction "(#HWB)PE2_33") (pintype "bidirectional"))
      (node (ref "UC_R4") (pin "2") (pinfunction "2_2") (pintype "passive"))
      (node (ref "U_MEGA32U-Q") (pin "33") (pinfunction "(#HWB)PE2_33") (pintype "bidirectional"))
    )
    (net (code "24") (name "/IO8") (class "Default")
      (node (ref "ATMEGA32U4-T") (pin "28") (pinfunction "(ADC11/PCINT4)PB4_28") (pintype "bidirectional"))
      (node (ref "U_MEGA32U-Q") (pin "28") (pinfunction "(ADC11/PCINT4)PB4_28") (pintype "bidirectional"))
    )
    (net (code "25") (name "/IO9*{slash}TH_DETECT") (class "Default")
      (node (ref "ATMEGA32U4-T") (pin "29") (pinfunction "(PCINT5/OC1A/#OC4B/ADC12)PB5_29") (pintype "bidirectional"))
      (node (ref "CTH_R1") (pin "2") (pinfunction "2_2") (pintype "passive"))
      (node (ref "U_MEGA32U-Q") (pin "29") (pinfunction "(PCINT5/OC1A/#OC4B/ADC12)PB5_29") (pintype "bidirectional"))
      (node (ref "U_TEMP-HUM") (pin "P$2") (pinfunction "P$2_P$2") (pintype "bidirectional"))
    )
    (net (code "26") (name "/IO10*{slash}BT_TX") (class "Default")
      (node (ref "ATMEGA32U4-T") (pin "30") (pinfunction "(PCINT6/OC1B/OC4B/ADC13)PB6_30") (pintype "bidirectional"))
      (node (ref "U_BT_TX") (pin "4") (pinfunction "Y_4") (pintype "bidirectional"))
      (node (ref "U_MEGA32U-Q") (pin "30") (pinfunction "(PCINT6/OC1B/OC4B/ADC13)PB6_30") (pintype "bidirectional"))
    )
    (net (code "27") (name "/IO11*{slash}BT_RX") (class "Default")
      (node (ref "ATMEGA32U4-T") (pin "12") (pinfunction "(PCINT7/OC0A/OC1C/#RTS)PB7_12") (pintype "bidirectional"))
      (node (ref "U_BT_RX") (pin "2") (pinfunction "A_2") (pintype "bidirectional"))
      (node (ref "U_MEGA32U-Q") (pin "12") (pinfunction "(PCINT7/OC0A/OC1C/#RTS)PB7_12") (pintype "bidirectional"))
    )
    (net (code "28") (name "/IO12") (class "Default")
      (node (ref "ATMEGA32U4-T") (pin "26") (pinfunction "(T1/#OC4D/ADC9)PD6_26") (pintype "bidirectional"))
      (node (ref "U_MEGA32U-Q") (pin "26") (pinfunction "(T1/#OC4D/ADC9)PD6_26") (pintype "bidirectional"))
    )
    (net (code "29") (name "/IO13*{slash}BT_LED") (class "Default")
      (node (ref "ATMEGA32U4-T") (pin "32") (pinfunction "(ICP3/CLK0/OC4A)PC7_32") (pintype "bidirectional"))
      (node (ref "LED_BT") (pin "ANODE") (pinfunction "AN_ANODE") (pintype "bidirectional"))
      (node (ref "U_MEGA32U-Q") (pin "32") (pinfunction "(ICP3/CLK0/OC4A)PC7_32") (pintype "bidirectional"))
    )
    (net (code "30") (name "/MISO") (class "Default")
      (node (ref "ATMEGA32U4-T") (pin "11") (pinfunction "(PD0/MISO/PCINT3)PB3_11") (pintype "bidirectional"))
      (node (ref "CON_ICSP") (pin "1") (pinfunction "1_1") (pintype "passive"))
      (node (ref "U_MEGA32U-Q") (pin "11") (pinfunction "(PD0/MISO/PCINT3)PB3_11") (pintype "bidirectional"))
    )
    (net (code "31") (name "/MOSI") (class "Default")
      (node (ref "ATMEGA32U4-T") (pin "10") (pinfunction "(PDI/MOSI/PCINT2)PB2_10") (pintype "bidirectional"))
      (node (ref "CON_ICSP") (pin "4") (pinfunction "4_4") (pintype "passive"))
      (node (ref "U_MEGA32U-Q") (pin "10") (pinfunction "(PDI/MOSI/PCINT2)PB2_10") (pintype "bidirectional"))
    )
    (net (code "32") (name "/RD+") (class "Default")
      (node (ref "ATMEGA32U4-T") (pin "4") (pinfunction "D+_4") (pintype "bidirectional"))
      (node (ref "U_MEGA32U-Q") (pin "4") (pinfunction "D+_4") (pintype "bidirectional"))
      (node (ref "U_R2") (pin "2") (pinfunction "2_2") (pintype "passive"))
    )
    (net (code "33") (name "/RD-") (class "Default")
      (node (ref "ATMEGA32U4-T") (pin "3") (pinfunction "D-_3") (pintype "bidirectional"))
      (node (ref "U_MEGA32U-Q") (pin "3") (pinfunction "D-_3") (pintype "bidirectional"))
      (node (ref "U_R1") (pin "2") (pinfunction "2_2") (pintype "passive"))
    )
    (net (code "34") (name "/RESET") (class "Default")
      (node (ref "ATMEGA32U4-T") (pin "13") (pinfunction "RESET_13") (pintype "input"))
      (node (ref "CON_ICSP") (pin "5") (pinfunction "5_5") (pintype "passive"))
      (node (ref "RESET_SWITCH") (pin "P3") (pinfunction "P$3_P3") (pintype "bidirectional"))
      (node (ref "RESET_SWITCH") (pin "P4") (pinfunction "P$4_P4") (pintype "bidirectional"))
      (node (ref "UC_R2") (pin "1") (pinfunction "1_1") (pintype "passive"))
      (node (ref "U_MEGA32U-Q") (pin "13") (pinfunction "RESET_13") (pintype "input"))
    )
    (net (code "35") (name "/RXLED") (class "Default")
      (node (ref "ATMEGA32U4-T") (pin "8") (pinfunction "(SS/PCINT0)PB0_8") (pintype "bidirectional"))
      (node (ref "U_MEGA32U-Q") (pin "8") (pinfunction "(SS/PCINT0)PB0_8") (pintype "bidirectional"))
    )
    (net (code "36") (name "/SCK") (class "Default")
      (node (ref "ATMEGA32U4-T") (pin "9") (pinfunction "(SCLK/PCINT1)PB1_9") (pintype "bidirectional"))
      (node (ref "CON_ICSP") (pin "3") (pinfunction "3_3") (pintype "passive"))
      (node (ref "U_MEGA32U-Q") (pin "9") (pinfunction "(SCLK/PCINT1)PB1_9") (pintype "bidirectional"))
    )
    (net (code "37") (name "/TXLED") (class "Default")
      (node (ref "ATMEGA32U4-T") (pin "22") (pinfunction "(XCK1/#CTS)PD5_22") (pintype "bidirectional"))
      (node (ref "U_MEGA32U-Q") (pin "22") (pinfunction "(XCK1/#CTS)PD5_22") (pintype "bidirectional"))
    )
    (net (code "38") (name "/UCAP") (class "Default")
      (node (ref "ATMEGA32U4-T") (pin "6") (pinfunction "UCAP_6") (pintype "passive"))
      (node (ref "UC_C7") (pin "1") (pinfunction "1_1") (pintype "passive"))
      (node (ref "U_MEGA32U-Q") (pin "6") (pinfunction "UCAP_6") (pintype "passive"))
    )
    (net (code "39") (name "/UGND") (class "Default")
      (node (ref "ATMEGA32U4-T") (pin "5") (pinfunction "UGND_5") (pintype "power_in"))
      (node (ref "CON_USB") (pin "T5") (pinfunction "T5_T5") (pintype "bidirectional"))
      (node (ref "UC_C7") (pin "2") (pinfunction "2_2") (pintype "passive"))
      (node (ref "UC_R3") (pin "2") (pinfunction "2_2") (pintype "passive"))
      (node (ref "U_FB1") (pin "P$2") (pinfunction "P$2_P$2") (pintype "passive"))
      (node (ref "U_MEGA32U-Q") (pin "5") (pinfunction "UGND_5") (pintype "power_in"))
    )
    (net (code "41") (name "/VEN") (class "Default")
      (node (ref "U_PUSHB") (pin "C1") (pinfunction "COM1_C1") (pintype "bidirectional"))
      (node (ref "U_PUSHB") (pin "C2") (pinfunction "COM2_C2") (pintype "bidirectional"))
      (node (ref "U_VR3") (pin "P$6") (pinfunction "EN_P$6") (pintype "bidirectional"))
      (node (ref "U_VR5") (pin "P$6") (pinfunction "EN_P$6") (pintype "bidirectional"))
      (node (ref "VR_R2") (pin "1") (pinfunction "1_1") (pintype "passive"))
    )
    (net (code "42") (name "/VFAN") (class "Default")
      (node (ref "CON_FAN") (pin "P1") (pinfunction "P1_P1") (pintype "bidirectional"))
      (node (ref "U_FANM") (pin "3") (pinfunction "P$3_3") (pintype "bidirectional"))
      (node (ref "VR_R4") (pin "2") (pinfunction "2_2") (pintype "passive"))
    )
    (net (code "44") (name "/VREG_IN") (class "Default")
      (node (ref "UR_C2") (pin "1") (pinfunction "1_1") (pintype "passive"))
      (node (ref "U_PUSHB") (pin "LS1") (pinfunction "LS1_LS1") (pintype "bidirectional"))
      (node (ref "U_PUSHB") (pin "LS2") (pinfunction "LS2_LS2") (pintype "bidirectional"))
      (node (ref "U_USB_CH") (pin "P$13") (pinfunction "OUT_P$13") (pintype "bidirectional"))
      (node (ref "U_VR3") (pin "P$5") (pinfunction "VIN_P$5") (pintype "bidirectional"))
      (node (ref "U_VR3") (pin "P$8") (pinfunction "VINA_P$8") (pintype "bidirectional"))
      (node (ref "U_VR5") (pin "P$5") (pinfunction "VIN_P$5") (pintype "bidirectional"))
      (node (ref "U_VR5") (pin "P$8") (pinfunction "VINA_P$8") (pintype "bidirectional"))
      (node (ref "VR3_0R2") (pin "1") (pinfunction "1_1") (pintype "passive"))
      (node (ref "VR3_C1") (pin "1") (pinfunction "1_1") (pintype "passive"))
      (node (ref "VR5_0R2") (pin "1") (pinfunction "1_1") (pintype "passive"))
      (node (ref "VR5_C1") (pin "1") (pinfunction "1_1") (pintype "passive"))
      (node (ref "VR5_C4") (pin "1") (pinfunction "1_1") (pintype "passive"))
      (node (ref "VR_C1") (pin "T+") (pinfunction "+_T+") (pintype "bidirectional"))
    )
    (net (code "45") (name "/V_BAT") (class "Default")
      (node (ref "CON_BAT") (pin "2") (pinfunction "+_2") (pintype "bidirectional"))
      (node (ref "UR_C1") (pin "1") (pinfunction "1_1") (pintype "passive"))
      (node (ref "U_USB_CH") (pin "P$12") (pinfunction "BAT_P$12") (pintype "bidirectional"))
      (node (ref "U_USB_CH") (pin "P$8") (pinfunction "ENBAT_P$8") (pintype "bidirectional"))
    )
    (net (code "46") (name "/XTAL1") (class "Default")
      (node (ref "ATMEGA32U4-T") (pin "17") (pinfunction "XTAL1_17") (pintype "bidirectional"))
      (node (ref "UC_C4") (pin "2") (pinfunction "2_2") (pintype "passive"))
      (node (ref "UC_CRYSTAL") (pin "1") (pinfunction "1_1") (pintype "passive"))
      (node (ref "UC_R1") (pin "1") (pinfunction "1_1") (pintype "passive"))
      (node (ref "U_MEGA32U-Q") (pin "17") (pinfunction "XTAL1_17") (pintype "bidirectional"))
    )
    (net (code "47") (name "/XTAL2") (class "Default")
      (node (ref "ATMEGA32U4-T") (pin "16") (pinfunction "XTAL2_16") (pintype "bidirectional"))
      (node (ref "UC_C3") (pin "2") (pinfunction "2_2") (pintype "passive"))
      (node (ref "UC_CRYSTAL") (pin "2") (pinfunction "2_2") (pintype "passive"))
      (node (ref "UC_R1") (pin "2") (pinfunction "2_2") (pintype "passive"))
      (node (ref "U_MEGA32U-Q") (pin "16") (pinfunction "XTAL2_16") (pintype "bidirectional"))
    )
    (net (code "48") (name "/XUSB") (class "Default")
      (node (ref "CON_USB") (pin "T1") (pinfunction "T1_T1") (pintype "bidirectional"))
      (node (ref "U_FB3") (pin "P$1") (pinfunction "P$1_P$1") (pintype "passive"))
    )
    (net (code "49") (name "3x2M_NM") (class "Default")
      (node (ref "ATMEGA32U4-T") (pin "15") (pinfunction "GND_15") (pintype "power_in"))
      (node (ref "ATMEGA32U4-T") (pin "23") (pinfunction "GND1_23") (pintype "power_in"))
      (node (ref "ATMEGA32U4-T") (pin "35") (pinfunction "GND2_35") (pintype "power_in"))
      (node (ref "ATMEGA32U4-T") (pin "43") (pinfunction "GND3_43") (pintype "power_in"))
      (node (ref "ATMEGA32U4-T") (pin "P$1") (pinfunction "PAD_P$1") (pintype "power_in"))
      (node (ref "BT_C1") (pin "2") (pinfunction "2_2") (pintype "passive"))
      (node (ref "BT_C2") (pin "2") (pinfunction "2_2") (pintype "passive"))
      (node (ref "CA_FB1") (pin "P$1") (pinfunction "P$1_P$1") (pintype "passive"))
      (node (ref "CD_C1") (pin "2") (pinfunction "2_2") (pintype "passive"))
      (node (ref "CE_C1") (pin "2") (pinfunction "2_2") (pintype "passive"))
      (node (ref "CON_BAT") (pin "1") (pinfunction "-_1") (pintype "bidirectional"))
      (node (ref "CON_BAT") (pin "NC1") (pinfunction "PAD1_NC1") (pintype "bidirectional"))
      (node (ref "CON_BAT") (pin "NC2") (pinfunction "PAD2_NC2") (pintype "bidirectional"))
      (node (ref "CON_DUST") (pin "P$1") (pinfunction "GND_P$1") (pintype "bidirectional"))
      (node (ref "CON_FAN") (pin "P2") (pinfunction "P2_P2") (pintype "bidirectional"))
      (node (ref "CON_FAN") (pin "PAD1") (pinfunction "PAD1_PAD1") (pintype "bidirectional"))
      (node (ref "CON_FAN") (pin "PAD2") (pinfunction "PAD2_PAD2") (pintype "bidirectional"))
      (node (ref "CON_ICSP") (pin "6") (pinfunction "6_6") (pintype "passive"))
      (node (ref "CON_USB") (pin "BPBL") (pinfunction "BPBL_BPBL") (pintype "bidirectional"))
      (node (ref "CON_USB") (pin "BPBR") (pinfunction "BPBR_BPBR") (pintype "bidirectional"))
      (node (ref "CON_USB") (pin "PBL") (pinfunction "PBL_PBL") (pintype "bidirectional"))
      (node (ref "CON_USB") (pin "PBL2") (pinfunction "PBL2_PBL2") (pintype "bidirectional"))
      (node (ref "CON_USB") (pin "PBR") (pinfunction "PBR_PBR") (pintype "bidirectional"))
      (node (ref "CON_USB") (pin "PBR2") (pinfunction "PBR2_PBR2") (pintype "bidirectional"))
      (node (ref "CON_USB") (pin "PTL") (pinfunction "PTL_PTL") (pintype "bidirectional"))
      (node (ref "CON_USB") (pin "PTR") (pinfunction "PTR_PTR") (pintype "bidirectional"))
      (node (ref "CTH_C1") (pin "2") (pinfunction "2_2") (pintype "passive"))
      (node (ref "RESET_SWITCH") (pin "P1") (pinfunction "P$1_P1") (pintype "bidirectional"))
      (node (ref "RESET_SWITCH") (pin "P2") (pinfunction "P$2_P2") (pintype "bidirectional"))
      (node (ref "R_LED_BT") (pin "1") (pinfunction "1_1") (pintype "passive"))
      (node (ref "UBT") (pin "P$13") (pinfunction "P$13_P$13") (pintype "bidirectional"))
      (node (ref "UBT") (pin "P$14") (pinfunction "P$14_P$14") (pintype "bidirectional"))
      (node (ref "UBT") (pin "P$19") (pinfunction "P$19_P$19") (pintype "bidirectional"))
      (node (ref "UBT") (pin "P$2") (pinfunction "P$2_P$2") (pintype "bidirectional"))
      (node (ref "UC_C1") (pin "2") (pinfunction "2_2") (pintype "passive"))
      (node (ref "UC_C2") (pin "2") (pinfunction "2_2") (pintype "passive"))
      (node (ref "UC_C3") (pin "1") (pinfunction "1_1") (pintype "passive"))
      (node (ref "UC_C4") (pin "1") (pinfunction "1_1") (pintype "passive"))
      (node (ref "UC_C5") (pin "2") (pinfunction "2_2") (pintype "passive"))
      (node (ref "UC_C6") (pin "2") (pinfunction "2_2") (pintype "passive"))
      (node (ref "UC_C8") (pin "2") (pinfunction "2_2") (pintype "passive"))
      (node (ref "UC_NTC") (pin "1") (pinfunction "P$1_1") (pintype "bidirectional"))
      (node (ref "UC_R3") (pin "1") (pinfunction "1_1") (pintype "passive"))
      (node (ref "UC_R4") (pin "1") (pinfunction "1_1") (pintype "passive"))
      (node (ref "UR_C1") (pin "2") (pinfunction "2_2") (pintype "passive"))
      (node (ref "UR_C2") (pin "2") (pinfunction "2_2") (pintype "passive"))
      (node (ref "U_BT_RX") (pin "1") (pinfunction "OE_N_1") (pintype "bidirectional"))
      (node (ref "U_BT_RX") (pin "3") (pinfunction "GND_3") (pintype "bidirectional"))
      (node (ref "U_BT_TX") (pin "1") (pinfunction "OE_N_1") (pintype "bidirectional"))
      (node (ref "U_BT_TX") (pin "3") (pinfunction "GND_3") (pintype "bidirectional"))
      (node (ref "U_C1") (pin "2") (pinfunction "2_2") (pintype "passive"))
      (node (ref "U_C3") (pin "2") (pinfunction "2_2") (pintype "passive"))
      (node (ref "U_C4") (pin "2") (pinfunction "2_2") (pintype "passive"))
      (node (ref "U_FB1") (pin "P$1") (pinfunction "P$1_P$1") (pintype "passive"))
      (node (ref "U_MEGA32U-Q") (pin "15") (pinfunction "GND_15") (pintype "power_in"))
      (node (ref "U_MEGA32U-Q") (pin "23") (pinfunction "GND1_23") (pintype "power_in"))
      (node (ref "U_MEGA32U-Q") (pin "35") (pinfunction "GND2_35") (pintype "power_in"))
      (node (ref "U_MEGA32U-Q") (pin "43") (pinfunction "GND3_43") (pintype "power_in"))
      (node (ref "U_MEGA32U-Q") (pin "EXP") (pinfunction "PAD_EXP") (pintype "power_in"))
      (node (ref "U_TEMP-HUM") (pin "P$4") (pinfunction "P$4_P$4") (pintype "bidirectional"))
      (node (ref "U_USB_CH") (pin "GND_PAD") (pinfunction "GND_PAD_GND_PAD") (pintype "bidirectional"))
      (node (ref "U_USB_CH") (pin "P$4") (pinfunction "GND_P$4") (pintype "bidirectional"))
      (node (ref "U_VR3") (pin "MID_PAD") (pinfunction "GND3_MID_PAD") (pintype "bidirectional"))
      (node (ref "U_VR3") (pin "P$3") (pinfunction "GND_P$3") (pintype "bidirectional"))
      (node (ref "U_VR3") (pin "P$9") (pinfunction "GND2_P$9") (pintype "bidirectional"))
      (node (ref "U_VR5") (pin "MID_PAD") (pinfunction "GND3_MID_PAD") (pintype "bidirectional"))
      (node (ref "U_VR5") (pin "P$3") (pinfunction "GND_P$3") (pintype "bidirectional"))
      (node (ref "U_VR5") (pin "P$9") (pinfunction "GND2_P$9") (pintype "bidirectional"))
      (node (ref "U_Z1") (pin "2") (pinfunction "2_2") (pintype "passive"))
      (node (ref "U_Z2") (pin "2") (pinfunction "2_2") (pintype "passive"))
      (node (ref "U_Z3") (pin "2") (pinfunction "2_2") (pintype "passive"))
      (node (ref "U_Z4") (pin "2") (pinfunction "2_2") (pintype "passive"))
      (node (ref "U_Z5") (pin "2") (pinfunction "2_2") (pintype "passive"))
      (node (ref "U_Z6") (pin "2") (pinfunction "2_2") (pintype "passive"))
      (node (ref "VR3_0R1") (pin "1") (pinfunction "1_1") (pintype "passive"))
      (node (ref "VR3_C1") (pin "2") (pinfunction "2_2") (pintype "passive"))
      (node (ref "VR3_C2") (pin "2") (pinfunction "2_2") (pintype "passive"))
      (node (ref "VR3_C3") (pin "2") (pinfunction "2_2") (pintype "passive"))
      (node (ref "VR3_R2") (pin "2") (pinfunction "2_2") (pintype "passive"))
      (node (ref "VR3_R4") (pin "2") (pinfunction "2_2") (pintype "passive"))
      (node (ref "VR3_R5") (pin "2") (pinfunction "2_2") (pintype "passive"))
      (node (ref "VR5_0R1") (pin "1") (pinfunction "1_1") (pintype "passive"))
      (node (ref "VR5_C1") (pin "2") (pinfunction "2_2") (pintype "passive"))
      (node (ref "VR5_C2") (pin "2") (pinfunction "2_2") (pintype "passive"))
      (node (ref "VR5_C3") (pin "2") (pinfunction "2_2") (pintype "passive"))
      (node (ref "VR5_C4") (pin "2") (pinfunction "2_2") (pintype "passive"))
      (node (ref "VR5_R2") (pin "2") (pinfunction "2_2") (pintype "passive"))
      (node (ref "VR_C1") (pin "T-") (pinfunction "-_T-") (pintype "bidirectional"))
      (node (ref "VR_R2") (pin "2") (pinfunction "2_2") (pintype "passive"))
    )
    (net (code "50") (name "Net-(CA_FB1-PadP$2)") (class "Default")
      (node (ref "CA_FB1") (pin "P$2") (pinfunction "P$2_P$2") (pintype "passive"))
      (node (ref "CON_EXTERN") (pin "B_5") (pinfunction "B_5_B_5") (pintype "bidirectional"))
      (node (ref "CON_EXTERN") (pin "T_5") (pinfunction "T_5_T_5") (pintype "bidirectional"))
    )
    (net (code "51") (name "Net-(LED_BT-CATH)") (class "Default")
      (node (ref "LED_BT") (pin "CATHODE") (pinfunction "CATH_CATHODE") (pintype "bidirectional"))
      (node (ref "R_LED_BT") (pin "2") (pinfunction "2_2") (pintype "passive"))
    )
    (net (code "52") (name "Net-(LED_CH-CATH)") (class "Default")
      (node (ref "LED_CH") (pin "CATHODE") (pinfunction "CATH_CATHODE") (pintype "bidirectional"))
      (node (ref "R_LED_CH") (pin "2") (pinfunction "2_2") (pintype "passive"))
    )
    (net (code "53") (name "Net-(UC_NTC-P$2)") (class "Default")
      (node (ref "UC_NTC") (pin "2") (pinfunction "P$2_2") (pintype "bidirectional"))
      (node (ref "UC_R6") (pin "1") (pinfunction "1_1") (pintype "passive"))
      (node (ref "U_USB_CH") (pin "P$11") (pinfunction "TS_P$11") (pintype "bidirectional"))
    )
    (net (code "54") (name "Net-(U_USB_CH-ADPSET)") (class "Default")
      (node (ref "U_USB_CH") (pin "P$1") (pinfunction "ADPSET_P$1") (pintype "bidirectional"))
      (node (ref "VR3_R5") (pin "1") (pinfunction "1_1") (pintype "passive"))
    )
    (net (code "55") (name "Net-(U_USB_CH-CT)") (class "Default")
      (node (ref "U_C1") (pin "1") (pinfunction "1_1") (pintype "passive"))
      (node (ref "U_USB_CH") (pin "P$14") (pinfunction "CT_P$14") (pintype "bidirectional"))
    )
    (net (code "56") (name "Net-(U_USB_CH-STAT1_N)") (class "Default")
      (node (ref "R_LED_CH") (pin "1") (pinfunction "1_1") (pintype "passive"))
      (node (ref "U_USB_CH") (pin "P$3") (pinfunction "STAT1_N_P$3") (pintype "bidirectional"))
    )
    (net (code "57") (name "Net-(U_USB_CH-TERM)") (class "Default")
      (node (ref "U_USB_CH") (pin "P$10") (pinfunction "TERM_P$10") (pintype "bidirectional"))
      (node (ref "VR3_R4") (pin "1") (pinfunction "1_1") (pintype "passive"))
    )
    (net (code "58") (name "Net-(U_VR3-FB)") (class "Default")
      (node (ref "U_VR3") (pin "P$10") (pinfunction "FB_P$10") (pintype "bidirectional"))
      (node (ref "VR3_R1") (pin "2") (pinfunction "2_2") (pintype "passive"))
      (node (ref "VR3_R2") (pin "1") (pinfunction "1_1") (pintype "passive"))
    )
    (net (code "59") (name "Net-(U_VR3-LX1)") (class "Default")
      (node (ref "U_VR3") (pin "P$4") (pinfunction "LX1_P$4") (pintype "bidirectional"))
      (node (ref "VR3_L1") (pin "2") (pinfunction "2_2") (pintype "passive"))
    )
    (net (code "60") (name "Net-(U_VR3-LX2)") (class "Default")
      (node (ref "U_VR3") (pin "P$2") (pinfunction "LX2_P$2") (pintype "bidirectional"))
      (node (ref "VR3_L1") (pin "1") (pinfunction "1_1") (pintype "passive"))
    )
    (net (code "61") (name "Net-(U_VR3-PS)") (class "Default")
      (node (ref "U_VR3") (pin "P$7") (pinfunction "PS_P$7") (pintype "bidirectional"))
      (node (ref "VR3_0R1") (pin "2") (pinfunction "2_2") (pintype "passive"))
      (node (ref "VR3_0R2") (pin "2") (pinfunction "2_2") (pintype "passive"))
    )
    (net (code "62") (name "Net-(U_VR5-FB)") (class "Default")
      (node (ref "U_VR5") (pin "P$10") (pinfunction "FB_P$10") (pintype "bidirectional"))
      (node (ref "VR5_R1") (pin "2") (pinfunction "2_2") (pintype "passive"))
      (node (ref "VR5_R2") (pin "1") (pinfunction "1_1") (pintype "passive"))
    )
    (net (code "63") (name "Net-(U_VR5-LX1)") (class "Default")
      (node (ref "U_VR5") (pin "P$4") (pinfunction "LX1_P$4") (pintype "bidirectional"))
      (node (ref "VR5_L1") (pin "2") (pinfunction "2_2") (pintype "passive"))
    )
    (net (code "64") (name "Net-(U_VR5-LX2)") (class "Default")
      (node (ref "U_VR5") (pin "P$2") (pinfunction "LX2_P$2") (pintype "bidirectional"))
      (node (ref "VR5_L1") (pin "1") (pinfunction "1_1") (pintype "passive"))
    )
    (net (code "65") (name "Net-(U_VR5-PS)") (class "Default")
      (node (ref "U_VR5") (pin "P$7") (pinfunction "PS_P$7") (pintype "bidirectional"))
      (node (ref "VR5_0R1") (pin "2") (pinfunction "2_2") (pintype "passive"))
      (node (ref "VR5_0R2") (pin "2") (pinfunction "2_2") (pintype "passive"))
    )
    (net (code "66") (name "VUSB") (class "Default")
      (node (ref "ATMEGA32U4-T") (pin "7") (pinfunction "VBUS_7") (pintype "input"))
      (node (ref "LED_CH") (pin "ANODE") (pinfunction "AN_ANODE") (pintype "bidirectional"))
      (node (ref "UC_R6") (pin "2") (pinfunction "2_2") (pintype "passive"))
      (node (ref "U_C3") (pin "1") (pinfunction "1_1") (pintype "passive"))
      (node (ref "U_C4") (pin "1") (pinfunction "1_1") (pintype "passive"))
      (node (ref "U_FB3") (pin "P$2") (pinfunction "P$2_P$2") (pintype "passive"))
      (node (ref "U_MEGA32U-Q") (pin "7") (pinfunction "VBUS_7") (pintype "input"))
      (node (ref "U_USB_CH") (pin "P$2") (pinfunction "ADP_P$2") (pintype "bidirectional"))
      (node (ref "U_USB_CH") (pin "P$6") (pinfunction "EN_P$6") (pintype "bidirectional"))
      (node (ref "U_USB_CH") (pin "P$7") (pinfunction "ENO_P$7") (pintype "bidirectional"))
    )
    (net (code "67") (name "unconnected-(CON_DUST-NC-PadP$4)") (class "Default")
      (node (ref "CON_DUST") (pin "P$4") (pinfunction "NC_P$4") (pintype "bidirectional"))
    )
    (net (code "68") (name "unconnected-(CON_USB-PadT4)") (class "Default")
      (node (ref "CON_USB") (pin "T4") (pinfunction "T4_T4") (pintype "bidirectional"))
    )
    (net (code "69") (name "unconnected-(UBT-PadP$1)") (class "Default")
      (node (ref "UBT") (pin "P$1") (pinfunction "P$1_P$1") (pintype "bidirectional"))
    )
    (net (code "70") (name "unconnected-(UBT-PadP$3)") (class "Default")
      (node (ref "UBT") (pin "P$3") (pinfunction "P$3_P$3") (pintype "bidirectional"))
    )
    (net (code "71") (name "unconnected-(UBT-PadP$4)") (class "Default")
      (node (ref "UBT") (pin "P$4") (pinfunction "P$4_P$4") (pintype "bidirectional"))
    )
    (net (code "72") (name "unconnected-(UBT-PadP$5)") (class "Default")
      (node (ref "UBT") (pin "P$5") (pinfunction "P$5_P$5") (pintype "bidirectional"))
    )
    (net (code "73") (name "unconnected-(UBT-PadP$6)") (class "Default")
      (node (ref "UBT") (pin "P$6") (pinfunction "P$6_P$6") (pintype "bidirectional"))
    )
    (net (code "74") (name "unconnected-(UBT-PadP$7)") (class "Default")
      (node (ref "UBT") (pin "P$7") (pinfunction "P$7_P$7") (pintype "bidirectional"))
    )
    (net (code "75") (name "unconnected-(UBT-PadP$8)") (class "Default")
      (node (ref "UBT") (pin "P$8") (pinfunction "P$8_P$8") (pintype "bidirectional"))
    )
    (net (code "76") (name "unconnected-(UBT-PadP$9)") (class "Default")
      (node (ref "UBT") (pin "P$9") (pinfunction "P$9_P$9") (pintype "bidirectional"))
    )
    (net (code "77") (name "unconnected-(UBT-PadP$10)") (class "Default")
      (node (ref "UBT") (pin "P$10") (pinfunction "P$10_P$10") (pintype "bidirectional"))
    )
    (net (code "78") (name "unconnected-(UBT-PadP$11)") (class "Default")
      (node (ref "UBT") (pin "P$11") (pinfunction "P$11_P$11") (pintype "bidirectional"))
    )
    (net (code "79") (name "unconnected-(UBT-PadP$15)") (class "Default")
      (node (ref "UBT") (pin "P$15") (pinfunction "P$15_P$15") (pintype "bidirectional"))
    )
    (net (code "80") (name "unconnected-(UBT-PadP$16)") (class "Default")
      (node (ref "UBT") (pin "P$16") (pinfunction "P$16_P$16") (pintype "bidirectional"))
    )
    (net (code "81") (name "unconnected-(UBT-PadP$17)") (class "Default")
      (node (ref "UBT") (pin "P$17") (pinfunction "P$17_P$17") (pintype "bidirectional"))
    )
    (net (code "82") (name "unconnected-(UBT-PadP$18)") (class "Default")
      (node (ref "UBT") (pin "P$18") (pinfunction "P$18_P$18") (pintype "bidirectional"))
    )
    (net (code "83") (name "unconnected-(UBT-PadP$22)") (class "Default")
      (node (ref "UBT") (pin "P$22") (pinfunction "P$22_P$22") (pintype "bidirectional"))
    )
    (net (code "84") (name "unconnected-(UBT-PadP$23)") (class "Default")
      (node (ref "UBT") (pin "P$23") (pinfunction "P$23_P$23") (pintype "bidirectional"))
    )
    (net (code "85") (name "unconnected-(UBT-PadP$24)") (class "Default")
      (node (ref "UBT") (pin "P$24") (pinfunction "P$24_P$24") (pintype "bidirectional"))
    )
    (net (code "86") (name "unconnected-(UBT-PadP$25)") (class "Default")
      (node (ref "UBT") (pin "P$25") (pinfunction "P$25_P$25") (pintype "bidirectional"))
    )
    (net (code "87") (name "unconnected-(UBT-PadP$26)") (class "Default")
      (node (ref "UBT") (pin "P$26") (pinfunction "P$26_P$26") (pintype "bidirectional"))
    )
    (net (code "88") (name "unconnected-(UBT-PadP$27)") (class "Default")
      (node (ref "UBT") (pin "P$27") (pinfunction "P$27_P$27") (pintype "bidirectional"))
    )
    (net (code "89") (name "unconnected-(UBT-PadP$28)") (class "Default")
      (node (ref "UBT") (pin "P$28") (pinfunction "P$28_P$28") (pintype "bidirectional"))
    )
    (net (code "90") (name "unconnected-(UBT-PadP$29)") (class "Default")
      (node (ref "UBT") (pin "P$29") (pinfunction "P$29_P$29") (pintype "bidirectional"))
    )
    (net (code "91") (name "unconnected-(UBT-PadP$30)") (class "Default")
      (node (ref "UBT") (pin "P$30") (pinfunction "P$30_P$30") (pintype "bidirectional"))
    )
    (net (code "92") (name "unconnected-(UBT-PadP$31)") (class "Default")
      (node (ref "UBT") (pin "P$31") (pinfunction "P$31_P$31") (pintype "bidirectional"))
    )
    (net (code "93") (name "unconnected-(UBT-PadP$32)") (class "Default")
      (node (ref "UBT") (pin "P$32") (pinfunction "P$32_P$32") (pintype "bidirectional"))
    )
    (net (code "94") (name "unconnected-(U_PUSHB-PadM1)") (class "Default")
      (node (ref "U_PUSHB") (pin "M1") (pinfunction "M1_M1") (pintype "bidirectional"))
    )
    (net (code "95") (name "unconnected-(U_PUSHB-PadM2)") (class "Default")
      (node (ref "U_PUSHB") (pin "M2") (pinfunction "M2_M2") (pintype "bidirectional"))
    )
    (net (code "96") (name "unconnected-(U_PUSHB-PadRS1)") (class "Default")
      (node (ref "U_PUSHB") (pin "RS1") (pinfunction "RS1_RS1") (pintype "bidirectional"))
    )
    (net (code "97") (name "unconnected-(U_PUSHB-PadRS2)") (class "Default")
      (node (ref "U_PUSHB") (pin "RS2") (pinfunction "RS2_RS2") (pintype "bidirectional"))
    )
    (net (code "98") (name "unconnected-(U_TEMP-HUM-PadP$3)") (class "Default")
      (node (ref "U_TEMP-HUM") (pin "P$3") (pinfunction "P$3_P$3") (pintype "bidirectional"))
    )
    (net (code "99") (name "unconnected-(U_USB_CH-CHRADP-PadP$9)") (class "Default")
      (node (ref "U_USB_CH") (pin "P$9") (pinfunction "CHRADP_P$9") (pintype "bidirectional"))
    )
    (net (code "100") (name "unconnected-(U_USB_CH-STAT2_N-PadP$5)") (class "Default")
      (node (ref "U_USB_CH") (pin "P$5") (pinfunction "STAT2_N_P$5") (pintype "bidirectional"))
    )
  )
)
